# AS5048A-Breakout.net
KiCad netlist of a schematic drawn in Altium Designer
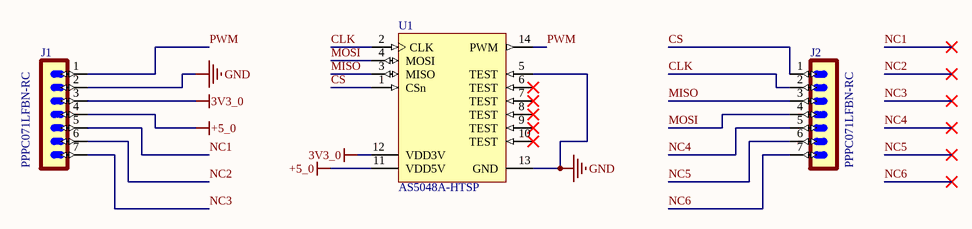
[diagram p0: AS5048A-Breakout.SchDoc]

(export (version "E")
  (design (tool "Eeschema 10.0.6"))
  (components
    (comp (ref "J1")
      (value "PPPC071LFBN-RC")
      (footprint "1X07-PIN")
      (description "7 Position Header Connector 0.100 (2.54mm) Through Hole Gold")
      (fields (field (name "MF") "Sullins Connector"))
      (libsource (lib "") (part "PPPC071LFBN-RC_1"))
    )
    (comp (ref "J2")
      (value "PPPC071LFBN-RC")
      (footprint "1X07-PIN")
      (description "7 Position Header Connector 0.100 (2.54mm) Through Hole Gold")
      (fields (field (name "MF") "Sullins Connector"))
      (libsource (lib "WUST") (part "PPPC071LFBN-RC"))
    )
    (comp (ref "U1")
      (value "AS5048A-HTSP")
      (footprint "AMS-TSSOP-14-5000X4400DE_L")
      (description "Magnetic Rotary Encoder 14-bit Angular Position Sensor, 3.3 or 5 V, TSSOP-14, Pb-Free, Reel")
      (fields (field (name "MANUFACTURER") "AMS"))
      (libsource (lib "Altium Content Vault") (part "AMS-AS5048A-TSSOP-14"))
    )
  )
  (nets
    (net (code "1") (name "+5_0") (class "Default")
      (node (ref "J1") (pin "4") (pinfunction "P$4_4") (pintype "bidirectional"))
      (node (ref "U1") (pin "11") (pinfunction "VDD5V_11") (pintype "power_in"))
    )
    (net (code "2") (name "/CLK") (class "Default")
      (node (ref "J2") (pin "2") (pinfunction "P$2_2") (pintype "bidirectional"))
      (node (ref "U1") (pin "2") (pinfunction "CLK_2") (pintype "input"))
    )
    (net (code "3") (name "/CS") (class "Default")
      (node (ref "J2") (pin "1") (pinfunction "P$1_1") (pintype "bidirectional"))
      (node (ref "U1") (pin "1") (pinfunction "CSn_1") (pintype "input"))
    )
    (net (code "4") (name "/MISO") (class "Default")
      (node (ref "J2") (pin "3") (pinfunction "P$3_3") (pintype "bidirectional"))
      (node (ref "U1") (pin "3") (pinfunction "MISO_3") (pintype "bidirectional"))
    )
    (net (code "5") (name "/MOSI") (class "Default")
      (node (ref "J2") (pin "4") (pinfunction "P$4_4") (pintype "bidirectional"))
      (node (ref "U1") (pin "4") (pinfunction "MOSI_4") (pintype "bidirectional"))
    )
    (net (code "6") (name "/NC1") (class "Default")
      (node (ref "J1") (pin "5") (pinfunction "P$5_5") (pintype "bidirectional"))
    )
    (net (code "7") (name "/NC2") (class "Default")
      (node (ref "J1") (pin "6") (pinfunction "P$6_6") (pintype "bidirectional"))
    )
    (net (code "8") (name "/NC3") (class "Default")
      (node (ref "J1") (pin "7") (pinfunction "P$7_7") (pintype "bidirectional"))
    )
    (net (code "9") (name "/NC4") (class "Default")
      (node (ref "J2") (pin "5") (pinfunction "P$5_5") (pintype "bidirectional"))
    )
    (net (code "10") (name "/NC5") (class "Default")
      (node (ref "J2") (pin "6") (pinfunction "P$6_6") (pintype "bidirectional"))
    )
    (net (code "11") (name "/NC6") (class "Default")
      (node (ref "J2") (pin "7") (pinfunction "P$7_7") (pintype "bidirectional"))
    )
    (net (code "12") (name "/PWM") (class "Default")
      (node (ref "J1") (pin "1") (pinfunction "P$1_1") (pintype "bidirectional"))
      (node (ref "U1") (pin "14") (pinfunction "PWM_14") (pintype "output"))
    )
    (net (code "13") (name "3V3_0") (class "Default")
      (node (ref "J1") (pin "3") (pinfunction "P$3_3") (pintype "bidirectional"))
      (node (ref "U1") (pin "12") (pinfunction "VDD3V_12") (pintype "power_in"))
    )
    (net (code "14") (name "GND") (class "Default")
      (node (ref "J1") (pin "2") (pinfunction "P$2_2") (pintype "bidirectional"))
      (node (ref "U1") (pin "13") (pinfunction "GND_13") (pintype "power_in"))
      (node (ref "U1") (pin "5") (pinfunction "TEST_5") (pintype "input"))
    )
    (net (code "15") (name "unconnected-(U1-TEST-Pad6)") (class "Default")
      (node (ref "U1") (pin "6") (pinfunction "TEST_6") (pintype "input+no_connect"))
    )
    (net (code "16") (name "unconnected-(U1-TEST-Pad7)") (class "Default")
      (node (ref "U1") (pin "7") (pinfunction "TEST_7") (pintype "input+no_connect"))
    )
    (net (code "17") (name "unconnected-(U1-TEST-Pad8)") (class "Default")
      (node (ref "U1") (pin "8") (pinfunction "TEST_8") (pintype "input+no_connect"))
    )
    (net (code "18") (name "unconnected-(U1-TEST-Pad9)") (class "Default")
      (node (ref "U1") (pin "9") (pinfunction "TEST_9") (pintype "input+no_connect"))
    )
    (net (code "19") (name "unconnected-(U1-TEST-Pad10)") (class "Default")
      (node (ref "U1") (pin "10") (pinfunction "TEST_10") (pintype "input+no_connect"))
    )
  )
)
